# digital_module.net
KiCad netlist of a schematic drawn in EAGLE
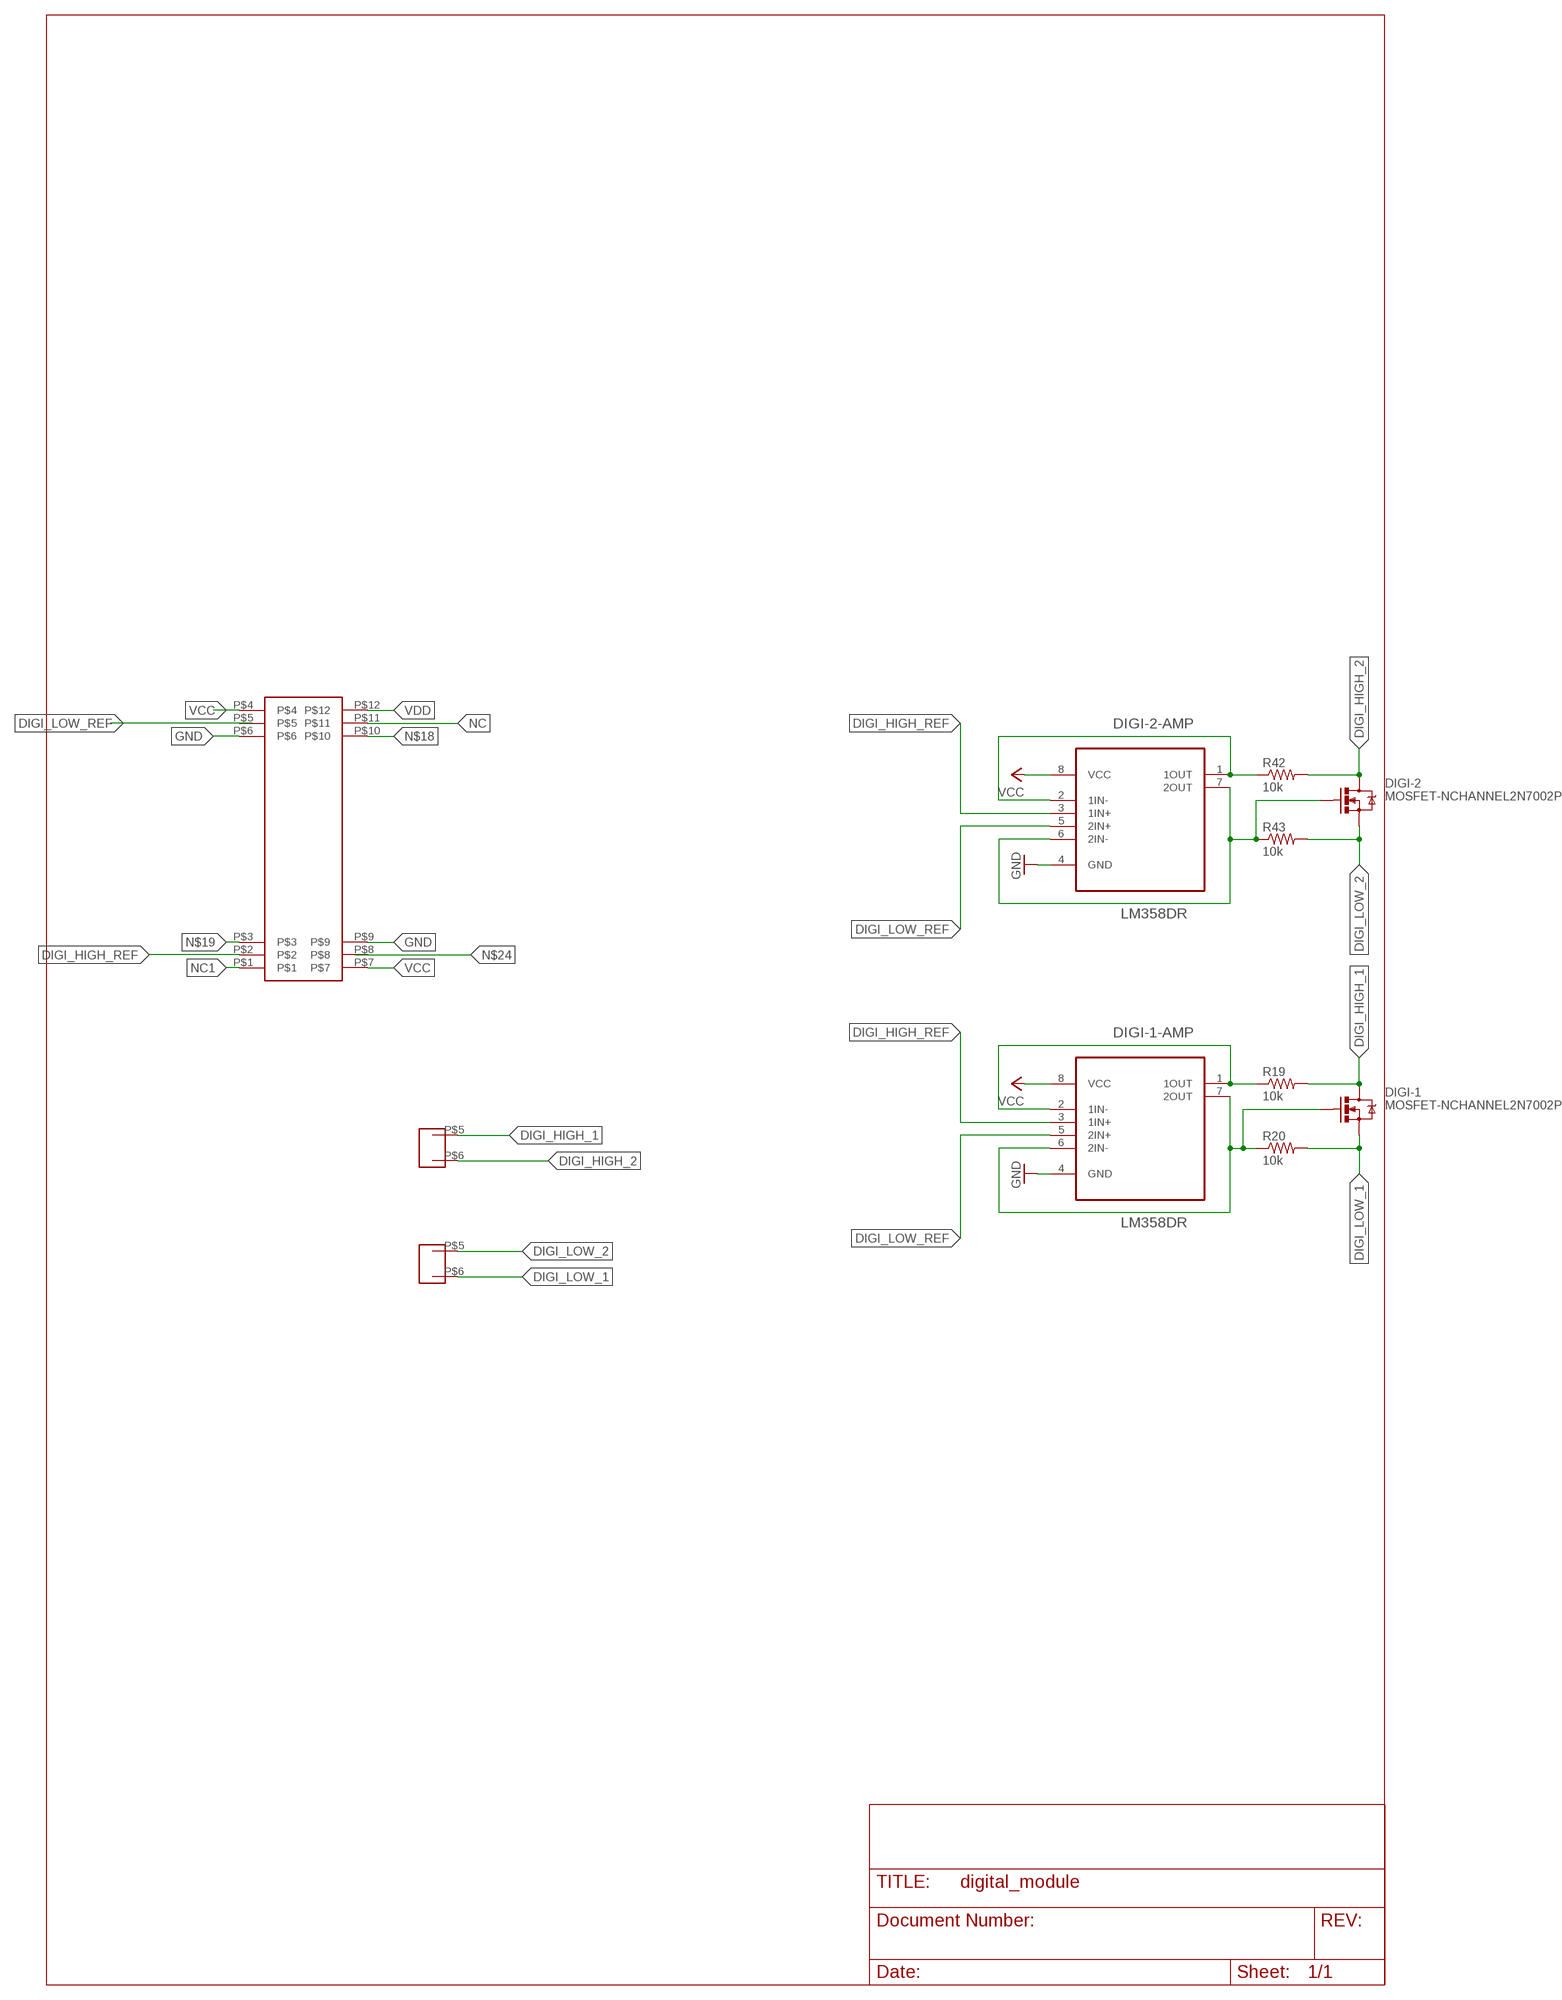
[diagram p0: schematic, sheet 1]

(export (version "E")
  (design (tool "Eeschema 10.0.6"))
  (components
    (comp (ref "DIGI-1")
      (value "MOSFET-NCHANNEL2N7002PW")
      (footprint "eagle-import:SOT323")
      (libsource (lib "eagle-import") (part "MOSFET-NCHANNEL2N7002PW"))
    )
    (comp (ref "DIGI-1-AMP")
      (value "LM358DR")
      (footprint "eagle-import:SOIC127P600X175-8N")
      (libsource (lib "eagle-import") (part "LM358DR"))
    )
    (comp (ref "DIGI-2")
      (value "MOSFET-NCHANNEL2N7002PW")
      (footprint "eagle-import:SOT323")
      (libsource (lib "eagle-import") (part "MOSFET-NCHANNEL2N7002PW"))
    )
    (comp (ref "DIGI-2-AMP")
      (value "LM358DR")
      (footprint "eagle-import:SOIC127P600X175-8N")
      (libsource (lib "eagle-import") (part "LM358DR"))
    )
    (comp (ref "R19")
      (value "10k")
      (footprint "eagle-import:R0805")
      (libsource (lib "eagle-import") (part "R-US_R0805"))
    )
    (comp (ref "R20")
      (value "10k")
      (footprint "eagle-import:R0805")
      (libsource (lib "eagle-import") (part "R-US_R0805"))
    )
    (comp (ref "R42")
      (value "10k")
      (footprint "eagle-import:R0805")
      (libsource (lib "eagle-import") (part "R-US_R0805"))
    )
    (comp (ref "R43")
      (value "10k")
      (footprint "eagle-import:R0805")
      (libsource (lib "eagle-import") (part "R-US_R0805"))
    )
    (comp (ref "U$1")
      (value "MODULE_CONNECTOR")
      (footprint "eagle-import:MODULE_CONNECTOR")
      (libsource (lib "eagle-import") (part "MODULE_CONNECTOR"))
    )
    (comp (ref "U$2")
      (value "5.08PITCHTERMINAL")
      (footprint "eagle-import:10KPL508")
      (libsource (lib "eagle-import") (part "5.08PITCHTERMINAL"))
    )
    (comp (ref "U$3")
      (value "5.08PITCHTERMINAL")
      (footprint "eagle-import:10KPL508")
      (libsource (lib "eagle-import") (part "5.08PITCHTERMINAL"))
    )
  )
  (nets
    (net (code "1") (name "DIGI_HIGH_1") (class "Default")
      (node (ref "DIGI-1") (pin "3") (pinfunction "D_3") (pintype "passive"))
      (node (ref "R19") (pin "2") (pinfunction "2_2") (pintype "passive"))
      (node (ref "U$2") (pin "P$5") (pinfunction "P$5_P$5") (pintype "bidirectional"))
    )
    (net (code "2") (name "DIGI_HIGH_2") (class "Default")
      (node (ref "DIGI-2") (pin "3") (pinfunction "D_3") (pintype "passive"))
      (node (ref "R42") (pin "2") (pinfunction "2_2") (pintype "passive"))
      (node (ref "U$2") (pin "P$6") (pinfunction "P$6_P$6") (pintype "bidirectional"))
    )
    (net (code "3") (name "DIGI_HIGH_REF") (class "Default")
      (node (ref "DIGI-1-AMP") (pin "3") (pinfunction "1IN+_3") (pintype "input"))
      (node (ref "DIGI-2-AMP") (pin "3") (pinfunction "1IN+_3") (pintype "input"))
      (node (ref "U$1") (pin "P$2") (pinfunction "P$2_P$2") (pintype "bidirectional"))
    )
    (net (code "4") (name "DIGI_LOW_1") (class "Default")
      (node (ref "DIGI-1") (pin "2") (pinfunction "S_2") (pintype "passive"))
      (node (ref "R20") (pin "2") (pinfunction "2_2") (pintype "passive"))
      (node (ref "U$3") (pin "P$6") (pinfunction "P$6_P$6") (pintype "bidirectional"))
    )
    (net (code "5") (name "DIGI_LOW_2") (class "Default")
      (node (ref "DIGI-2") (pin "2") (pinfunction "S_2") (pintype "passive"))
      (node (ref "R43") (pin "2") (pinfunction "2_2") (pintype "passive"))
      (node (ref "U$3") (pin "P$5") (pinfunction "P$5_P$5") (pintype "bidirectional"))
    )
    (net (code "6") (name "DIGI_LOW_REF") (class "Default")
      (node (ref "DIGI-1-AMP") (pin "5") (pinfunction "2IN+_5") (pintype "input"))
      (node (ref "DIGI-2-AMP") (pin "5") (pinfunction "2IN+_5") (pintype "input"))
    )
    (net (code "7") (name "GND") (class "Default")
      (node (ref "DIGI-1-AMP") (pin "4") (pinfunction "GND_4") (pintype "passive"))
      (node (ref "DIGI-2-AMP") (pin "4") (pinfunction "GND_4") (pintype "passive"))
      (node (ref "U$1") (pin "P$6") (pinfunction "P$6_P$6") (pintype "bidirectional"))
      (node (ref "U$1") (pin "P$9") (pinfunction "P$9_P$9") (pintype "bidirectional"))
    )
    (net (code "8") (name "N$18") (class "Default")
      (node (ref "U$1") (pin "P$10") (pinfunction "P$10_P$10") (pintype "bidirectional"))
    )
    (net (code "9") (name "N$19") (class "Default")
      (node (ref "U$1") (pin "P$3") (pinfunction "P$3_P$3") (pintype "bidirectional"))
    )
    (net (code "11") (name "NC") (class "Default")
      (node (ref "U$1") (pin "P$11") (pinfunction "P$11_P$11") (pintype "bidirectional"))
    )
    (net (code "12") (name "NC1") (class "Default")
      (node (ref "U$1") (pin "P$1") (pinfunction "P$1_P$1") (pintype "bidirectional"))
    )
    (net (code "13") (name "Net-(DIGI-1-AMP-1IN-)") (class "Default")
      (node (ref "DIGI-1-AMP") (pin "1") (pinfunction "1OUT_1") (pintype "output"))
      (node (ref "DIGI-1-AMP") (pin "2") (pinfunction "1IN-_2") (pintype "input"))
      (node (ref "R19") (pin "1") (pinfunction "1_1") (pintype "passive"))
    )
    (net (code "14") (name "Net-(DIGI-1-AMP-2IN-)") (class "Default")
      (node (ref "DIGI-1") (pin "1") (pinfunction "G_1") (pintype "passive"))
      (node (ref "DIGI-1-AMP") (pin "6") (pinfunction "2IN-_6") (pintype "input"))
      (node (ref "DIGI-1-AMP") (pin "7") (pinfunction "2OUT_7") (pintype "output"))
      (node (ref "R20") (pin "1") (pinfunction "1_1") (pintype "passive"))
    )
    (net (code "15") (name "Net-(DIGI-2-AMP-1IN-)") (class "Default")
      (node (ref "DIGI-2-AMP") (pin "1") (pinfunction "1OUT_1") (pintype "output"))
      (node (ref "DIGI-2-AMP") (pin "2") (pinfunction "1IN-_2") (pintype "input"))
      (node (ref "R42") (pin "1") (pinfunction "1_1") (pintype "passive"))
    )
    (net (code "16") (name "Net-(DIGI-2-AMP-2IN-)") (class "Default")
      (node (ref "DIGI-2") (pin "1") (pinfunction "G_1") (pintype "passive"))
      (node (ref "DIGI-2-AMP") (pin "6") (pinfunction "2IN-_6") (pintype "input"))
      (node (ref "DIGI-2-AMP") (pin "7") (pinfunction "2OUT_7") (pintype "output"))
      (node (ref "R43") (pin "1") (pinfunction "1_1") (pintype "passive"))
    )
    (net (code "17") (name "VCC") (class "Default")
      (node (ref "DIGI-1-AMP") (pin "8") (pinfunction "VCC_8") (pintype "power_in"))
      (node (ref "DIGI-2-AMP") (pin "8") (pinfunction "VCC_8") (pintype "power_in"))
      (node (ref "U$1") (pin "P$4") (pinfunction "P$4_P$4") (pintype "bidirectional"))
      (node (ref "U$1") (pin "P$7") (pinfunction "P$7_P$7") (pintype "bidirectional"))
    )
    (net (code "18") (name "VDD") (class "Default")
      (node (ref "U$1") (pin "P$12") (pinfunction "P$12_P$12") (pintype "bidirectional"))
    )
    (net (code "19") (name "unconnected-(U$1-PadP$5)") (class "Default")
      (node (ref "U$1") (pin "P$5") (pinfunction "P$5_P$5") (pintype "bidirectional"))
    )
    (net (code "20") (name "unconnected-(U$1-PadP$8)") (class "Default")
      (node (ref "U$1") (pin "P$8") (pinfunction "P$8_P$8") (pintype "bidirectional"))
    )
  )
)
